# ESP12E_BMS_Low_Voltage.net
KiCad netlist of a schematic drawn in EAGLE
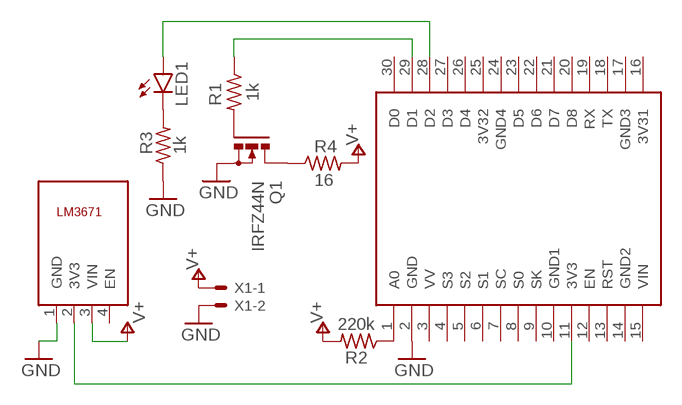
[diagram p0: schematic, sheet 1]

(export (version "E")
  (design (tool "Eeschema 10.0.6"))
  (components
    (comp (ref "LED1")
      (value "TLLR4400")
      (footprint "eagle-import:LED3MM")
      (fields (field (name "MF") "VISHAY SEMICONDUCTOR"))
      (libsource (lib "eagle-import") (part "TLLR4400"))
    )
    (comp (ref "Q1")
      (value "IRFZ44N")
      (footprint "eagle-import:TO220BH")
      (libsource (lib "eagle-import") (part "PMOSFET_NTO220BH"))
    )
    (comp (ref "R1")
      (value "1k")
      (footprint "eagle-import:0204_7")
      (libsource (lib "eagle-import") (part "R-US_0204/7"))
    )
    (comp (ref "R2")
      (value "220k")
      (footprint "eagle-import:0204_7")
      (libsource (lib "eagle-import") (part "R-US_0204/7"))
    )
    (comp (ref "R3")
      (value "1k")
      (footprint "eagle-import:0204_7")
      (libsource (lib "eagle-import") (part "R-US_0204/7"))
    )
    (comp (ref "R4")
      (value "16")
      (footprint "eagle-import:P0613_15")
      (libsource (lib "eagle-import") (part "R-US_0613/15"))
    )
    (comp (ref "U$1")
      (value "NODEMCU")
      (footprint "eagle-import:NODEMCU")
      (libsource (lib "eagle-import") (part "NODEMCU"))
    )
    (comp (ref "U$2")
      (value "LM3671")
      (footprint "eagle-import:LM3671")
      (libsource (lib "eagle-import") (part "LM3671"))
    )
    (comp (ref "X1")
      (value "JST-XH-02-PIN-ROUND-PAD")
      (footprint "eagle-import:JST-XH-02-PACKAGE-ROUND-PAD")
      (libsource (lib "eagle-import") (part "JST-XH-02-PIN-ROUND-PAD"))
    )
  )
  (nets
    (net (code "1") (name "/3V31") (class "Default")
      (node (ref "U$1") (pin "16") (pinfunction "3V31_16") (pintype "power_in"))
    )
    (net (code "2") (name "/3V32") (class "Default")
      (node (ref "U$1") (pin "25") (pinfunction "3V32_25") (pintype "power_in"))
    )
    (net (code "3") (name "/GND1") (class "Default")
      (node (ref "U$1") (pin "10") (pinfunction "GND1_10") (pintype "power_in"))
    )
    (net (code "4") (name "/GND2") (class "Default")
      (node (ref "U$1") (pin "14") (pinfunction "GND2_14") (pintype "power_in"))
    )
    (net (code "5") (name "/GND3") (class "Default")
      (node (ref "U$1") (pin "17") (pinfunction "GND3_17") (pintype "power_in"))
    )
    (net (code "6") (name "/GND4") (class "Default")
      (node (ref "U$1") (pin "24") (pinfunction "GND4_24") (pintype "power_in"))
    )
    (net (code "7") (name "GND") (class "Default")
      (node (ref "Q1") (pin "S") (pinfunction "S_S") (pintype "passive"))
      (node (ref "R3") (pin "1") (pinfunction "1_1") (pintype "passive"))
      (node (ref "U$1") (pin "2") (pinfunction "GND_2") (pintype "power_in"))
      (node (ref "U$2") (pin "1") (pinfunction "GND_1") (pintype "power_in"))
      (node (ref "X1") (pin "2") (pinfunction "S_2") (pintype "passive"))
    )
    (net (code "8") (name "Net-(LED1-C)") (class "Default")
      (node (ref "LED1") (pin "K") (pinfunction "C_K") (pintype "passive"))
      (node (ref "R3") (pin "2") (pinfunction "2_2") (pintype "passive"))
    )
    (net (code "9") (name "Net-(Q1-PadD)") (class "Default")
      (node (ref "Q1") (pin "D") (pinfunction "D_D") (pintype "passive"))
      (node (ref "R4") (pin "1") (pinfunction "1_1") (pintype "passive"))
    )
    (net (code "10") (name "Net-(Q1-PadG)") (class "Default")
      (node (ref "Q1") (pin "G") (pinfunction "G_G") (pintype "passive"))
      (node (ref "R1") (pin "2") (pinfunction "2_2") (pintype "passive"))
    )
    (net (code "11") (name "Net-(U$1-3V3)") (class "Default")
      (node (ref "U$1") (pin "11") (pinfunction "3V3_11") (pintype "power_in"))
      (node (ref "U$2") (pin "2") (pinfunction "3V3_2") (pintype "power_in"))
    )
    (net (code "12") (name "Net-(U$1-A0)") (class "Default")
      (node (ref "R2") (pin "1") (pinfunction "1_1") (pintype "passive"))
      (node (ref "U$1") (pin "1") (pinfunction "A0_1") (pintype "bidirectional"))
    )
    (net (code "13") (name "Net-(U$1-D1)") (class "Default")
      (node (ref "R1") (pin "1") (pinfunction "1_1") (pintype "passive"))
      (node (ref "U$1") (pin "29") (pinfunction "D1_29") (pintype "bidirectional"))
    )
    (net (code "14") (name "Net-(U$1-D2)") (class "Default")
      (node (ref "LED1") (pin "A") (pinfunction "A_A") (pintype "passive"))
      (node (ref "U$1") (pin "28") (pinfunction "D2_28") (pintype "bidirectional"))
    )
    (net (code "15") (name "V+") (class "Default")
      (node (ref "R2") (pin "2") (pinfunction "2_2") (pintype "passive"))
      (node (ref "R4") (pin "2") (pinfunction "2_2") (pintype "passive"))
      (node (ref "U$2") (pin "3") (pinfunction "VIN_3") (pintype "power_in"))
      (node (ref "X1") (pin "1") (pinfunction "S_1") (pintype "passive"))
    )
    (net (code "16") (name "unconnected-(U$1-D0-Pad30)") (class "Default")
      (node (ref "U$1") (pin "30") (pinfunction "D0_30") (pintype "bidirectional"))
    )
    (net (code "17") (name "unconnected-(U$1-D3-Pad27)") (class "Default")
      (node (ref "U$1") (pin "27") (pinfunction "D3_27") (pintype "bidirectional"))
    )
    (net (code "18") (name "unconnected-(U$1-D4-Pad26)") (class "Default")
      (node (ref "U$1") (pin "26") (pinfunction "D4_26") (pintype "bidirectional"))
    )
    (net (code "19") (name "unconnected-(U$1-D5-Pad23)") (class "Default")
      (node (ref "U$1") (pin "23") (pinfunction "D5_23") (pintype "bidirectional"))
    )
    (net (code "20") (name "unconnected-(U$1-D6-Pad22)") (class "Default")
      (node (ref "U$1") (pin "22") (pinfunction "D6_22") (pintype "bidirectional"))
    )
    (net (code "21") (name "unconnected-(U$1-D7-Pad21)") (class "Default")
      (node (ref "U$1") (pin "21") (pinfunction "D7_21") (pintype "bidirectional"))
    )
    (net (code "22") (name "unconnected-(U$1-D8-Pad20)") (class "Default")
      (node (ref "U$1") (pin "20") (pinfunction "D8_20") (pintype "bidirectional"))
    )
    (net (code "23") (name "unconnected-(U$1-EN-Pad12)") (class "Default")
      (node (ref "U$1") (pin "12") (pinfunction "EN_12") (pintype "bidirectional"))
    )
    (net (code "24") (name "unconnected-(U$1-RST-Pad13)") (class "Default")
      (node (ref "U$1") (pin "13") (pinfunction "RST_13") (pintype "bidirectional"))
    )
    (net (code "25") (name "unconnected-(U$1-RX-Pad19)") (class "Default")
      (node (ref "U$1") (pin "19") (pinfunction "RX_19") (pintype "bidirectional"))
    )
    (net (code "26") (name "unconnected-(U$1-S0-Pad8)") (class "Default")
      (node (ref "U$1") (pin "8") (pinfunction "S0_8") (pintype "bidirectional"))
    )
    (net (code "27") (name "unconnected-(U$1-S1-Pad6)") (class "Default")
      (node (ref "U$1") (pin "6") (pinfunction "S1_6") (pintype "bidirectional"))
    )
    (net (code "28") (name "unconnected-(U$1-S2-Pad5)") (class "Default")
      (node (ref "U$1") (pin "5") (pinfunction "S2_5") (pintype "bidirectional"))
    )
    (net (code "29") (name "unconnected-(U$1-S3-Pad4)") (class "Default")
      (node (ref "U$1") (pin "4") (pinfunction "S3_4") (pintype "bidirectional"))
    )
    (net (code "30") (name "unconnected-(U$1-SC-Pad7)") (class "Default")
      (node (ref "U$1") (pin "7") (pinfunction "SC_7") (pintype "bidirectional"))
    )
    (net (code "31") (name "unconnected-(U$1-SK-Pad9)") (class "Default")
      (node (ref "U$1") (pin "9") (pinfunction "SK_9") (pintype "bidirectional"))
    )
    (net (code "32") (name "unconnected-(U$1-TX-Pad18)") (class "Default")
      (node (ref "U$1") (pin "18") (pinfunction "TX_18") (pintype "bidirectional"))
    )
    (net (code "33") (name "unconnected-(U$1-VIN-Pad15)") (class "Default")
      (node (ref "U$1") (pin "15") (pinfunction "VIN_15") (pintype "bidirectional"))
    )
    (net (code "34") (name "unconnected-(U$1-VV-Pad3)") (class "Default")
      (node (ref "U$1") (pin "3") (pinfunction "VV_3") (pintype "bidirectional"))
    )
    (net (code "35") (name "unconnected-(U$2-EN-Pad4)") (class "Default")
      (node (ref "U$2") (pin "4") (pinfunction "EN_4") (pintype "input"))
    )
  )
)
